# ESP32.net
KiCad netlist of a schematic drawn in Altium Designer
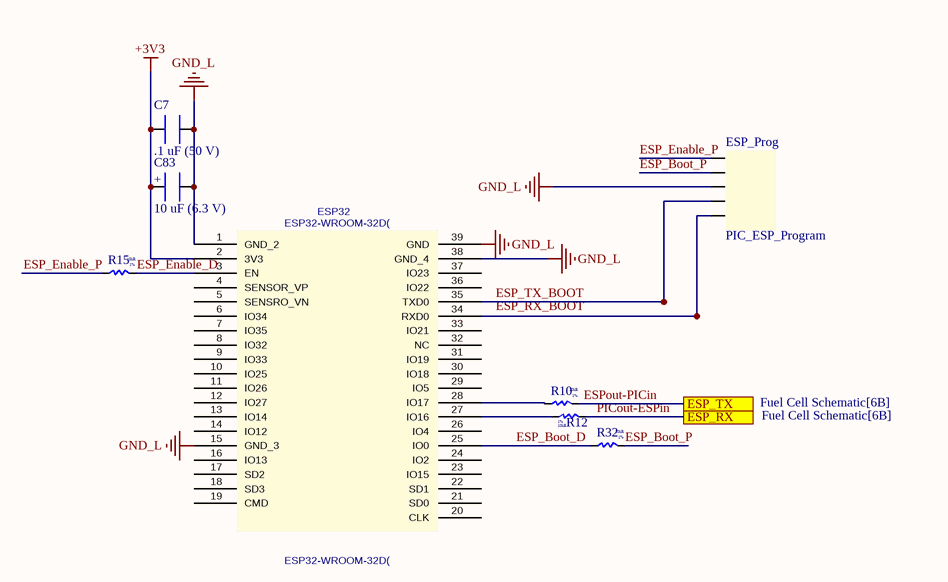
[diagram p0: ESP32.SchDoc]

(export (version "E")
  (design (tool "Eeschema 10.0.6"))
  (components
    (comp (ref "C7")
      (value ".1 uF (50 V)")
      (footprint ".1uF capacitor")
      (libsource (lib "Schlib1") (part ".1 uF cap"))
    )
    (comp (ref "C83")
      (value "10 uF (6.3 V)")
      (footprint "10 uF cap")
      (libsource (lib "Schlib1") (part "10 uF cap"))
    )
    (comp (ref "ESP32")
      (value "ESP32-WROOM-32D(")
      (footprint "ESP32")
      (fields
        (field (name "MANUFACTURER_PART_NUMBER") "ESP32-WROOM-32D(M113DH6400PH3Q0)")
        (field (name "ALTIUM_VALUE") "ESP32-WROOM-32D(")
        (field (name "COPYRIGHT") "Copyright (C) 2023 Ultra Librarian. All rights reserved.")
      )
      (libsource (lib "Schlib1") (part "ESP32-WROOM-32D("))
    )
    (comp (ref "ESP_Prog")
      (value "PIC_ESP_Program")
      (footprint "ESP_Program")
      (libsource (lib "Schlib1") (part "PIC_ESP_Program"))
    )
    (comp (ref "R10")
      (value "~")
      (footprint "Resistor_YAGEO_0805")
      (description "RES 10K OHM 1% 1/8W 0805")
      (fields
        (field (name "MANUFACTURER") "Yageo")
        (field (name "MANUFACTURER PART NUMBER") "RC0805FR-1010KL")
        (field (name "TOLERANCE") "1%")
        (field (name "RESISTANCE") "10kR")
      )
      (libsource (lib "Schlib1") (part "RC0805FR-1010KL"))
    )
    (comp (ref "R12")
      (value "~")
      (footprint "Resistor_YAGEO_0805")
      (description "RES 10K OHM 1% 1/8W 0805")
      (fields
        (field (name "MANUFACTURER") "Yageo")
        (field (name "MANUFACTURER PART NUMBER") "RC0805FR-1010KL")
        (field (name "TOLERANCE") "1%")
        (field (name "RESISTANCE") "10kR")
      )
      (libsource (lib "Schlib1") (part "RC0805FR-1010KL"))
    )
    (comp (ref "R15")
      (value "~")
      (footprint "Resistor_YAGEO_0805")
      (description "RES 10K OHM 1% 1/8W 0805")
      (fields
        (field (name "MANUFACTURER") "Yageo")
        (field (name "MANUFACTURER PART NUMBER") "RC0805FR-1010KL")
        (field (name "TOLERANCE") "1%")
        (field (name "RESISTANCE") "10kR")
      )
      (libsource (lib "Schlib1") (part "RC0805FR-1010KL"))
    )
    (comp (ref "R32")
      (value "~")
      (footprint "Resistor_YAGEO_0805")
      (description "RES 10K OHM 1% 1/8W 0805")
      (fields
        (field (name "MANUFACTURER") "Yageo")
        (field (name "MANUFACTURER PART NUMBER") "RC0805FR-1010KL")
        (field (name "TOLERANCE") "1%")
        (field (name "RESISTANCE") "10kR")
      )
      (libsource (lib "Schlib1") (part "RC0805FR-1010KL"))
    )
  )
  (nets
    (net (code "1") (name "+3V3") (class "Default")
      (node (ref "C7") (pin "1") (pinfunction "1_1") (pintype "passive"))
      (node (ref "C83") (pin "1") (pinfunction "1_1") (pintype "passive"))
      (node (ref "ESP32") (pin "2") (pinfunction "3V3_2") (pintype "passive"))
    )
    (net (code "2") (name "/ESP_Boot_D") (class "Default")
      (node (ref "ESP32") (pin "25") (pinfunction "IO0_25") (pintype "passive"))
      (node (ref "R32") (pin "1") (pinfunction "1_1") (pintype "passive"))
    )
    (net (code "3") (name "/ESP_Boot_P") (class "Default")
      (node (ref "ESP_Prog") (pin "4") (pinfunction "Boot_4") (pintype "passive"))
      (node (ref "R32") (pin "2") (pinfunction "2_2") (pintype "passive"))
    )
    (net (code "4") (name "/ESP_Enable_D") (class "Default")
      (node (ref "ESP32") (pin "3") (pinfunction "EN_3") (pintype "passive"))
      (node (ref "R15") (pin "2") (pinfunction "2_2") (pintype "passive"))
    )
    (net (code "5") (name "/ESP_Enable_P") (class "Default")
      (node (ref "ESP_Prog") (pin "5") (pinfunction "Enable_5") (pintype "passive"))
      (node (ref "R15") (pin "1") (pinfunction "1_1") (pintype "passive"))
    )
    (net (code "7") (name "/ESP_TX_BOOT") (class "Default")
      (node (ref "ESP32") (pin "35") (pinfunction "TXD0_35") (pintype "passive"))
      (node (ref "ESP_Prog") (pin "2") (pinfunction "RX_2") (pintype "passive"))
    )
    (net (code "8") (name "/ESPout-PICin") (class "Default")
      (node (ref "R10") (pin "2") (pinfunction "2_2") (pintype "passive"))
    )
    (net (code "9") (name "/PICout-ESPin") (class "Default")
      (node (ref "R12") (pin "2") (pinfunction "2_2") (pintype "passive"))
    )
    (net (code "10") (name "GND_L") (class "Default")
      (node (ref "C7") (pin "2") (pinfunction "2_2") (pintype "passive"))
      (node (ref "C83") (pin "2") (pinfunction "2_2") (pintype "passive"))
      (node (ref "ESP32") (pin "1") (pinfunction "GND_2_1") (pintype "passive"))
      (node (ref "ESP32") (pin "15") (pinfunction "GND_3_15") (pintype "passive"))
      (node (ref "ESP32") (pin "38") (pinfunction "GND_4_38") (pintype "passive"))
      (node (ref "ESP32") (pin "39") (pinfunction "GND_39") (pintype "passive"))
      (node (ref "ESP_Prog") (pin "3") (pinfunction "GND_3") (pintype "passive"))
    )
    (net (code "11") (name "Net-(ESP32-IO16)") (class "Default")
      (node (ref "ESP32") (pin "27") (pinfunction "IO16_27") (pintype "passive"))
      (node (ref "R12") (pin "1") (pinfunction "1_1") (pintype "passive"))
    )
    (net (code "12") (name "Net-(ESP32-IO17)") (class "Default")
      (node (ref "ESP32") (pin "28") (pinfunction "IO17_28") (pintype "passive"))
      (node (ref "R10") (pin "1") (pinfunction "1_1") (pintype "passive"))
    )
    (net (code "13") (name "Net-(ESP32-RXD0)") (class "Default")
      (node (ref "ESP32") (pin "34") (pinfunction "RXD0_34") (pintype "passive"))
      (node (ref "ESP_Prog") (pin "1") (pinfunction "TX_1") (pintype "passive"))
    )
    (net (code "14") (name "unconnected-(ESP32-CLK-Pad20)") (class "Default")
      (node (ref "ESP32") (pin "20") (pinfunction "CLK_20") (pintype "passive"))
    )
    (net (code "15") (name "unconnected-(ESP32-CMD-Pad19)") (class "Default")
      (node (ref "ESP32") (pin "19") (pinfunction "CMD_19") (pintype "passive"))
    )
    (net (code "16") (name "unconnected-(ESP32-IO2-Pad24)") (class "Default")
      (node (ref "ESP32") (pin "24") (pinfunction "IO2_24") (pintype "passive"))
    )
    (net (code "17") (name "unconnected-(ESP32-IO4-Pad26)") (class "Default")
      (node (ref "ESP32") (pin "26") (pinfunction "IO4_26") (pintype "passive"))
    )
    (net (code "18") (name "unconnected-(ESP32-IO5-Pad29)") (class "Default")
      (node (ref "ESP32") (pin "29") (pinfunction "IO5_29") (pintype "passive"))
    )
    (net (code "19") (name "unconnected-(ESP32-IO12-Pad14)") (class "Default")
      (node (ref "ESP32") (pin "14") (pinfunction "IO12_14") (pintype "passive"))
    )
    (net (code "20") (name "unconnected-(ESP32-IO13-Pad16)") (class "Default")
      (node (ref "ESP32") (pin "16") (pinfunction "IO13_16") (pintype "passive"))
    )
    (net (code "21") (name "unconnected-(ESP32-IO14-Pad13)") (class "Default")
      (node (ref "ESP32") (pin "13") (pinfunction "IO14_13") (pintype "passive"))
    )
    (net (code "22") (name "unconnected-(ESP32-IO15-Pad23)") (class "Default")
      (node (ref "ESP32") (pin "23") (pinfunction "IO15_23") (pintype "passive"))
    )
    (net (code "23") (name "unconnected-(ESP32-IO18-Pad30)") (class "Default")
      (node (ref "ESP32") (pin "30") (pinfunction "IO18_30") (pintype "passive"))
    )
    (net (code "24") (name "unconnected-(ESP32-IO19-Pad31)") (class "Default")
      (node (ref "ESP32") (pin "31") (pinfunction "IO19_31") (pintype "passive"))
    )
    (net (code "25") (name "unconnected-(ESP32-IO21-Pad33)") (class "Default")
      (node (ref "ESP32") (pin "33") (pinfunction "IO21_33") (pintype "passive"))
    )
    (net (code "26") (name "unconnected-(ESP32-IO22-Pad36)") (class "Default")
      (node (ref "ESP32") (pin "36") (pinfunction "IO22_36") (pintype "passive"))
    )
    (net (code "27") (name "unconnected-(ESP32-IO23-Pad37)") (class "Default")
      (node (ref "ESP32") (pin "37") (pinfunction "IO23_37") (pintype "passive"))
    )
    (net (code "28") (name "unconnected-(ESP32-IO25-Pad10)") (class "Default")
      (node (ref "ESP32") (pin "10") (pinfunction "IO25_10") (pintype "passive"))
    )
    (net (code "29") (name "unconnected-(ESP32-IO26-Pad11)") (class "Default")
      (node (ref "ESP32") (pin "11") (pinfunction "IO26_11") (pintype "passive"))
    )
    (net (code "30") (name "unconnected-(ESP32-IO27-Pad12)") (class "Default")
      (node (ref "ESP32") (pin "12") (pinfunction "IO27_12") (pintype "passive"))
    )
    (net (code "31") (name "unconnected-(ESP32-IO32-Pad8)") (class "Default")
      (node (ref "ESP32") (pin "8") (pinfunction "IO32_8") (pintype "passive"))
    )
    (net (code "32") (name "unconnected-(ESP32-IO33-Pad9)") (class "Default")
      (node (ref "ESP32") (pin "9") (pinfunction "IO33_9") (pintype "passive"))
    )
    (net (code "33") (name "unconnected-(ESP32-IO34-Pad6)") (class "Default")
      (node (ref "ESP32") (pin "6") (pinfunction "IO34_6") (pintype "passive"))
    )
    (net (code "34") (name "unconnected-(ESP32-IO35-Pad7)") (class "Default")
      (node (ref "ESP32") (pin "7") (pinfunction "IO35_7") (pintype "passive"))
    )
    (net (code "35") (name "unconnected-(ESP32-NC-Pad32)") (class "Default")
      (node (ref "ESP32") (pin "32") (pinfunction "NC_32") (pintype "passive"))
    )
    (net (code "36") (name "unconnected-(ESP32-SD0-Pad21)") (class "Default")
      (node (ref "ESP32") (pin "21") (pinfunction "SD0_21") (pintype "passive"))
    )
    (net (code "37") (name "unconnected-(ESP32-SD1-Pad22)") (class "Default")
      (node (ref "ESP32") (pin "22") (pinfunction "SD1_22") (pintype "passive"))
    )
    (net (code "38") (name "unconnected-(ESP32-SD2-Pad17)") (class "Default")
      (node (ref "ESP32") (pin "17") (pinfunction "SD2_17") (pintype "passive"))
    )
    (net (code "39") (name "unconnected-(ESP32-SD3-Pad18)") (class "Default")
      (node (ref "ESP32") (pin "18") (pinfunction "SD3_18") (pintype "passive"))
    )
    (net (code "40") (name "unconnected-(ESP32-SENSOR_VP-Pad4)") (class "Default")
      (node (ref "ESP32") (pin "4") (pinfunction "SENSOR_VP_4") (pintype "passive"))
    )
    (net (code "41") (name "unconnected-(ESP32-SENSRO_VN-Pad5)") (class "Default")
      (node (ref "ESP32") (pin "5") (pinfunction "SENSRO_VN_5") (pintype "passive"))
    )
  )
)
